# output_stage.net
KiCad netlist of a schematic drawn in Altium Designer
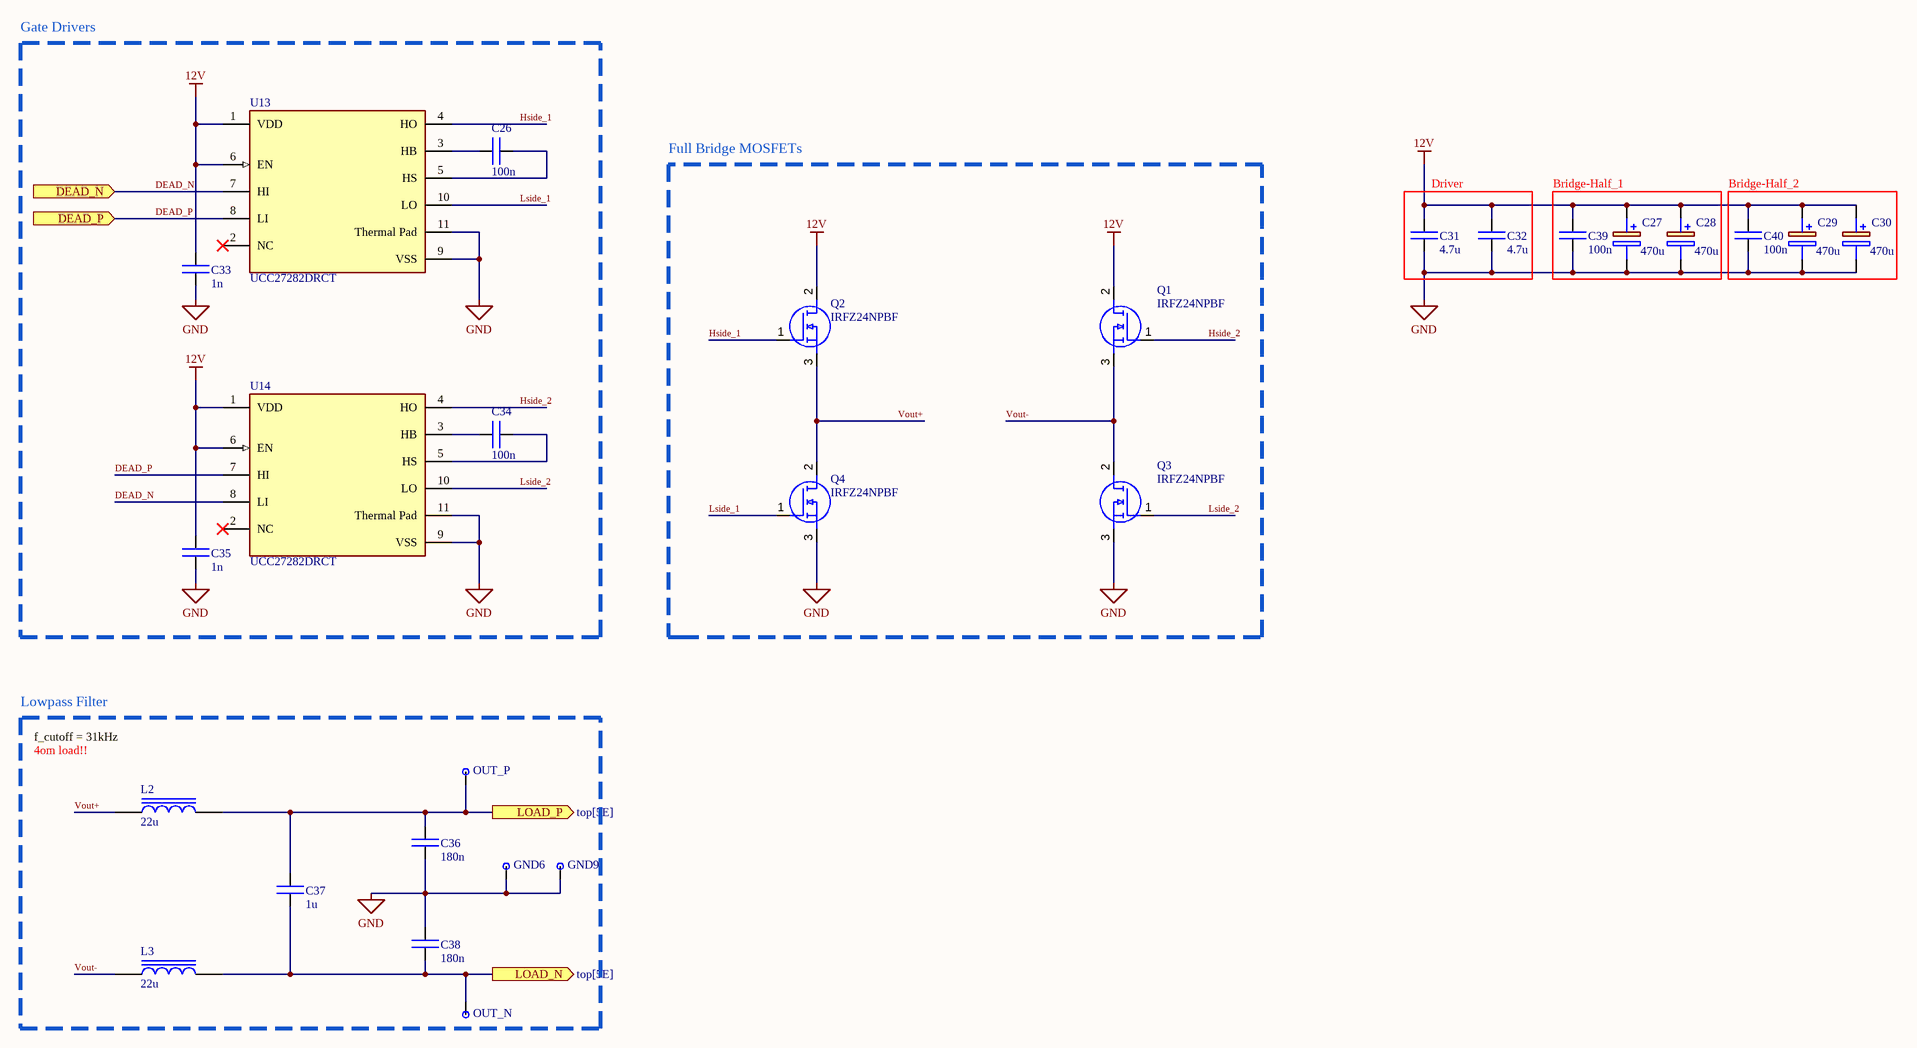
[diagram p0: output_stage.SchDoc]

(export (version "E")
  (design (tool "Eeschema 10.0.6"))
  (components
    (comp (ref "C26")
      (value "100n")
      (footprint "CAP_IPC_0805_133A")
      (libsource (lib "INT_lib") (part "Capacitor"))
    )
    (comp (ref "C27")
      (value "470u")
      (footprint "EEEFK1V331P")
      (description "Capacitor Polarised")
      (fields
        (field (name "MANUFACTURER_PART_NUMBER") "EEEFK1E471P")
        (field (name "MOUSER PART NUMBER") "667-EEE-FK1E471P")
      )
      (libsource (lib "INT_lib") (part "EEEFK1E471P"))
    )
    (comp (ref "C28")
      (value "470u")
      (footprint "EEEFK1V331P")
      (description "Capacitor Polarised")
      (fields
        (field (name "MANUFACTURER_PART_NUMBER") "EEEFK1E471P")
        (field (name "MOUSER PART NUMBER") "667-EEE-FK1E471P")
      )
      (libsource (lib "INT_lib") (part "EEEFK1E471P"))
    )
    (comp (ref "C29")
      (value "470u")
      (footprint "EEEFK1V331P")
      (description "Capacitor Polarised")
      (fields
        (field (name "MANUFACTURER_PART_NUMBER") "EEEFK1E471P")
        (field (name "MOUSER PART NUMBER") "667-EEE-FK1E471P")
      )
      (libsource (lib "INT_lib") (part "EEEFK1E471P"))
    )
    (comp (ref "C30")
      (value "470u")
      (footprint "EEEFK1V331P")
      (description "Capacitor Polarised")
      (fields
        (field (name "MANUFACTURER_PART_NUMBER") "EEEFK1E471P")
        (field (name "MOUSER PART NUMBER") "667-EEE-FK1E471P")
      )
      (libsource (lib "INT_lib") (part "EEEFK1E471P"))
    )
    (comp (ref "C31")
      (value "4.7u")
      (footprint "CAP_IPC_0805_133A")
      (libsource (lib "INT_lib") (part "Capacitor"))
    )
    (comp (ref "C32")
      (value "4.7u")
      (footprint "CAP_IPC_0805_133A")
      (libsource (lib "INT_lib") (part "Capacitor"))
    )
    (comp (ref "C33")
      (value "1n")
      (footprint "CAP_IPC_0805_133A")
      (libsource (lib "INT_lib") (part "Capacitor"))
    )
    (comp (ref "C34")
      (value "100n")
      (footprint "CAP_IPC_0805_133A")
      (libsource (lib "INT_lib") (part "Capacitor"))
    )
    (comp (ref "C35")
      (value "1n")
      (footprint "CAP_IPC_0805_133A")
      (libsource (lib "INT_lib") (part "Capacitor"))
    )
    (comp (ref "C36")
      (value "180n")
      (footprint "CAP_IPC_0805_133A")
      (fields (field (name "VOLTAGE") "50"))
      (libsource (lib "INT_lib") (part "Capacitor"))
    )
    (comp (ref "C37")
      (value "1u")
      (footprint "CAP_IPC_0805_133A")
      (fields (field (name "VOLTAGE") "50"))
      (libsource (lib "INT_lib") (part "Capacitor"))
    )
    (comp (ref "C38")
      (value "180n")
      (footprint "CAP_IPC_0805_133A")
      (fields (field (name "VOLTAGE") "50"))
      (libsource (lib "INT_lib") (part "Capacitor"))
    )
    (comp (ref "C39")
      (value "100n")
      (footprint "CAP_IPC_0805_133A")
      (libsource (lib "INT_lib") (part "Capacitor"))
    )
    (comp (ref "C40")
      (value "100n")
      (footprint "CAP_IPC_0805_133A")
      (libsource (lib "INT_lib") (part "Capacitor"))
    )
    (comp (ref "GND6")
      (value "TestPoint")
      (footprint "TestPoint_SMT")
      (description "Test Point")
      (libsource (lib "INT_lib") (part "TestPoint"))
    )
    (comp (ref "GND9")
      (value "TestPoint")
      (footprint "TestPoint_SMT")
      (description "Test Point")
      (libsource (lib "INT_lib") (part "TestPoint"))
    )
    (comp (ref "L2")
      (value "22u")
      (footprint "SRR1208-220ML")
      (description "Inductor SMD; 22uH; Ioperation: 3.5A; R: 43mΩ; ±20%; Isat: 4A")
      (fields (field (name "MANUFACTURER_PART_NUMBER") "SRR1208-220ML"))
      (libsource (lib "INT_lib") (part "SRR1208-220ML_inductor"))
    )
    (comp (ref "L3")
      (value "22u")
      (footprint "SRR1208-220ML")
      (description "Inductor SMD; 22uH; Ioperation: 3.5A; R: 43mΩ; ±20%; Isat: 4A")
      (fields (field (name "MANUFACTURER_PART_NUMBER") "SRR1208-220ML"))
      (libsource (lib "INT_lib") (part "SRR1208-220ML_inductor"))
    )
    (comp (ref "OUT_N")
      (value "TestPoint")
      (footprint "TestPoint_SMT")
      (description "Test Point")
      (libsource (lib "INT_lib") (part "TestPoint"))
    )
    (comp (ref "OUT_P")
      (value "TestPoint")
      (footprint "TestPoint_SMT")
      (description "Test Point")
      (libsource (lib "INT_lib") (part "TestPoint"))
    )
    (comp (ref "Q1")
      (value "IRFZ24NPBF")
      (footprint "IRFZ24NPBF")
      (description "HEXFET POWER MOSFET N-CHANNEL")
      (libsource (lib "INT_lib") (part "IRFZ24NPBF"))
    )
    (comp (ref "Q2")
      (value "IRFZ24NPBF")
      (footprint "IRFZ24NPBF")
      (description "HEXFET POWER MOSFET N-CHANNEL")
      (libsource (lib "INT_lib") (part "IRFZ24NPBF"))
    )
    (comp (ref "Q3")
      (value "IRFZ24NPBF")
      (footprint "IRFZ24NPBF")
      (description "HEXFET POWER MOSFET N-CHANNEL")
      (libsource (lib "INT_lib") (part "IRFZ24NPBF"))
    )
    (comp (ref "Q4")
      (value "IRFZ24NPBF")
      (footprint "IRFZ24NPBF")
      (description "HEXFET POWER MOSFET N-CHANNEL")
      (libsource (lib "INT_lib") (part "IRFZ24NPBF"))
    )
    (comp (ref "U13")
      (value "UCC27282DRCT")
      (footprint "UCC27282")
      (description "IC GATE DRVR HALF-BRIDGE 10VSON")
      (libsource (lib "INT_lib") (part "UCC27282DRCT"))
    )
    (comp (ref "U14")
      (value "UCC27282DRCT")
      (footprint "UCC27282")
      (description "IC GATE DRVR HALF-BRIDGE 10VSON")
      (libsource (lib "INT_lib") (part "UCC27282DRCT"))
    )
  )
  (nets
    (net (code "1") (name "/DEAD_N") (class "Default")
      (node (ref "U13") (pin "7") (pinfunction "HI_7") (pintype "passive"))
      (node (ref "U14") (pin "8") (pinfunction "LI_8") (pintype "passive"))
    )
    (net (code "2") (name "/DEAD_P") (class "Default")
      (node (ref "U13") (pin "8") (pinfunction "LI_8") (pintype "passive"))
      (node (ref "U14") (pin "7") (pinfunction "HI_7") (pintype "passive"))
    )
    (net (code "3") (name "/Hside_1") (class "Default")
      (node (ref "Q2") (pin "1") (pinfunction "G_1") (pintype "passive"))
      (node (ref "U13") (pin "4") (pinfunction "HO_4") (pintype "passive"))
    )
    (net (code "4") (name "/Hside_2") (class "Default")
      (node (ref "Q1") (pin "1") (pinfunction "G_1") (pintype "passive"))
      (node (ref "U14") (pin "4") (pinfunction "HO_4") (pintype "passive"))
    )
    (net (code "5") (name "/LOAD_N") (class "Default")
      (node (ref "C37") (pin "2") (pinfunction "2_2") (pintype "passive"))
      (node (ref "C38") (pin "2") (pinfunction "2_2") (pintype "passive"))
      (node (ref "L3") (pin "2") (pinfunction "2_2") (pintype "passive"))
      (node (ref "OUT_N") (pin "1") (pinfunction "1_1") (pintype "passive"))
    )
    (net (code "6") (name "/LOAD_P") (class "Default")
      (node (ref "C36") (pin "1") (pinfunction "1_1") (pintype "passive"))
      (node (ref "C37") (pin "1") (pinfunction "1_1") (pintype "passive"))
      (node (ref "L2") (pin "2") (pinfunction "2_2") (pintype "passive"))
      (node (ref "OUT_P") (pin "1") (pinfunction "1_1") (pintype "passive"))
    )
    (net (code "7") (name "/Lside_1") (class "Default")
      (node (ref "Q4") (pin "1") (pinfunction "G_1") (pintype "passive"))
      (node (ref "U13") (pin "10") (pinfunction "LO_10") (pintype "passive"))
    )
    (net (code "8") (name "/Lside_2") (class "Default")
      (node (ref "Q3") (pin "1") (pinfunction "G_1") (pintype "passive"))
      (node (ref "U14") (pin "10") (pinfunction "LO_10") (pintype "passive"))
    )
    (net (code "9") (name "/Vout+") (class "Default")
      (node (ref "L2") (pin "1") (pinfunction "1_1") (pintype "passive"))
      (node (ref "Q2") (pin "3") (pinfunction "S_3") (pintype "passive"))
      (node (ref "Q4") (pin "2") (pinfunction "D_2") (pintype "passive"))
    )
    (net (code "10") (name "/Vout-") (class "Default")
      (node (ref "L3") (pin "1") (pinfunction "1_1") (pintype "passive"))
      (node (ref "Q1") (pin "3") (pinfunction "S_3") (pintype "passive"))
      (node (ref "Q3") (pin "2") (pinfunction "D_2") (pintype "passive"))
    )
    (net (code "11") (name "12V") (class "Default")
      (node (ref "C27") (pin "1") (pinfunction "+_1") (pintype "passive"))
      (node (ref "C28") (pin "1") (pinfunction "+_1") (pintype "passive"))
      (node (ref "C29") (pin "1") (pinfunction "+_1") (pintype "passive"))
      (node (ref "C30") (pin "1") (pinfunction "+_1") (pintype "passive"))
      (node (ref "C31") (pin "1") (pinfunction "1_1") (pintype "passive"))
      (node (ref "C32") (pin "1") (pinfunction "1_1") (pintype "passive"))
      (node (ref "C33") (pin "2") (pinfunction "2_2") (pintype "passive"))
      (node (ref "C35") (pin "2") (pinfunction "2_2") (pintype "passive"))
      (node (ref "C39") (pin "1") (pinfunction "1_1") (pintype "passive"))
      (node (ref "C40") (pin "1") (pinfunction "1_1") (pintype "passive"))
      (node (ref "Q1") (pin "2") (pinfunction "D_2") (pintype "passive"))
      (node (ref "Q2") (pin "2") (pinfunction "D_2") (pintype "passive"))
      (node (ref "U13") (pin "1") (pinfunction "VDD_1") (pintype "power_in"))
      (node (ref "U13") (pin "6") (pinfunction "EN_6") (pintype "input"))
      (node (ref "U14") (pin "1") (pinfunction "VDD_1") (pintype "power_in"))
      (node (ref "U14") (pin "6") (pinfunction "EN_6") (pintype "input"))
    )
    (net (code "12") (name "GND") (class "Default")
      (node (ref "C27") (pin "2") (pinfunction "-_2") (pintype "passive"))
      (node (ref "C28") (pin "2") (pinfunction "-_2") (pintype "passive"))
      (node (ref "C29") (pin "2") (pinfunction "-_2") (pintype "passive"))
      (node (ref "C30") (pin "2") (pinfunction "-_2") (pintype "passive"))
      (node (ref "C31") (pin "2") (pinfunction "2_2") (pintype "passive"))
      (node (ref "C32") (pin "2") (pinfunction "2_2") (pintype "passive"))
      (node (ref "C33") (pin "1") (pinfunction "1_1") (pintype "passive"))
      (node (ref "C35") (pin "1") (pinfunction "1_1") (pintype "passive"))
      (node (ref "C36") (pin "2") (pinfunction "2_2") (pintype "passive"))
      (node (ref "C38") (pin "1") (pinfunction "1_1") (pintype "passive"))
      (node (ref "C39") (pin "2") (pinfunction "2_2") (pintype "passive"))
      (node (ref "C40") (pin "2") (pinfunction "2_2") (pintype "passive"))
      (node (ref "GND6") (pin "1") (pinfunction "1_1") (pintype "passive"))
      (node (ref "GND9") (pin "1") (pinfunction "1_1") (pintype "passive"))
      (node (ref "Q3") (pin "3") (pinfunction "S_3") (pintype "passive"))
      (node (ref "Q4") (pin "3") (pinfunction "S_3") (pintype "passive"))
      (node (ref "U13") (pin "11") (pinfunction "Thermal_Pad_11") (pintype "power_in"))
      (node (ref "U13") (pin "9") (pinfunction "VSS_9") (pintype "power_in"))
      (node (ref "U14") (pin "11") (pinfunction "Thermal_Pad_11") (pintype "power_in"))
      (node (ref "U14") (pin "9") (pinfunction "VSS_9") (pintype "power_in"))
    )
    (net (code "13") (name "Net-(U13-HB)") (class "Default")
      (node (ref "C26") (pin "1") (pinfunction "1_1") (pintype "passive"))
      (node (ref "U13") (pin "3") (pinfunction "HB_3") (pintype "passive"))
    )
    (net (code "14") (name "Net-(U13-HS)") (class "Default")
      (node (ref "C26") (pin "2") (pinfunction "2_2") (pintype "passive"))
      (node (ref "U13") (pin "5") (pinfunction "HS_5") (pintype "passive"))
    )
    (net (code "15") (name "Net-(U14-HB)") (class "Default")
      (node (ref "C34") (pin "1") (pinfunction "1_1") (pintype "passive"))
      (node (ref "U14") (pin "3") (pinfunction "HB_3") (pintype "passive"))
    )
    (net (code "16") (name "Net-(U14-HS)") (class "Default")
      (node (ref "C34") (pin "2") (pinfunction "2_2") (pintype "passive"))
      (node (ref "U14") (pin "5") (pinfunction "HS_5") (pintype "passive"))
    )
    (net (code "17") (name "unconnected-(U13-NC-Pad2)") (class "Default")
      (node (ref "U13") (pin "2") (pinfunction "NC_2") (pintype "passive+no_connect"))
    )
    (net (code "18") (name "unconnected-(U14-NC-Pad2)") (class "Default")
      (node (ref "U14") (pin "2") (pinfunction "NC_2") (pintype "passive+no_connect"))
    )
  )
)
